# Power_Supply.net
KiCad netlist of a schematic drawn in Altium Designer
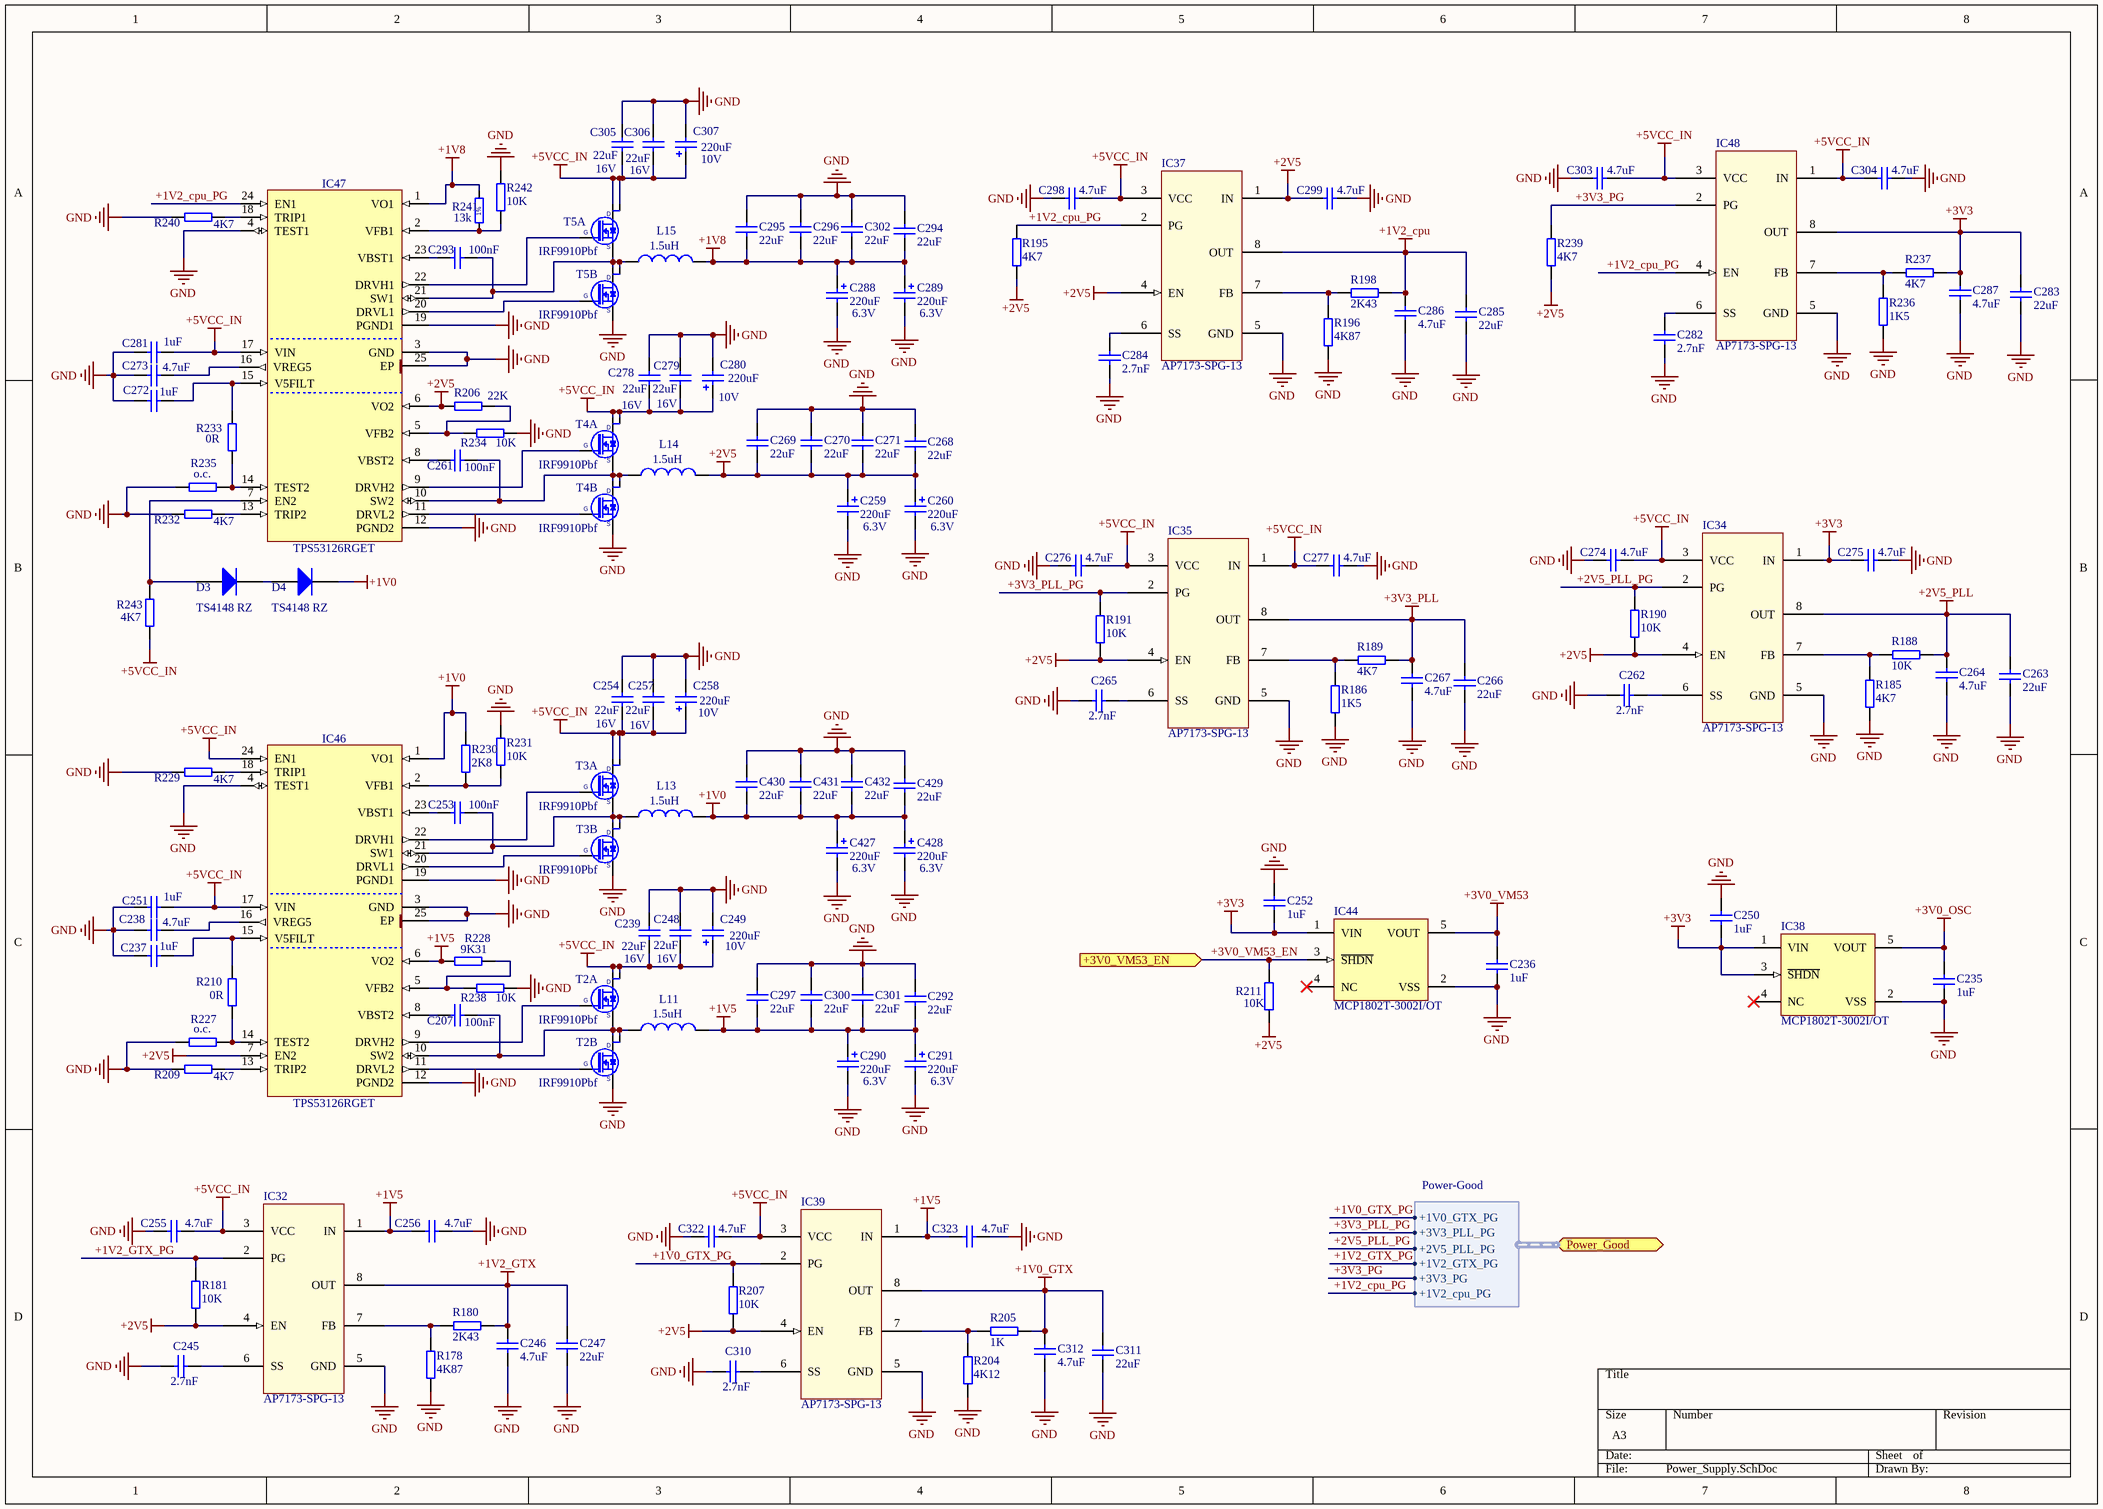
[diagram p0: Power_Supply.SchDoc]

(export (version "E")
  (design (tool "Eeschema 10.0.6"))
  (components
    (comp (ref "C207")
      (value "100nF")
      (footprint "CC1005-0402")
      (description "Capacitor")
      (fields
        (field (name "TOLERANCE") "±10%")
        (field (name "VOLTAGE") "16V")
        (field (name "PUBLISHER") "Altium Limited")
      )
      (libsource (lib "wr_switch") (part "Cap"))
    )
    (comp (ref "C235")
      (value "1uF")
      (footprint "CC1005-0402")
      (description "Capacitor")
      (fields
        (field (name "TOLERANCE") "±10%")
        (field (name "VOLTAGE") "16V")
        (field (name "PUBLISHER") "Altium Limited")
      )
      (libsource (lib "wr_switch") (part "Cap"))
    )
    (comp (ref "C236")
      (value "1uF")
      (footprint "CC1005-0402")
      (description "Capacitor")
      (fields
        (field (name "TOLERANCE") "±10%")
        (field (name "VOLTAGE") "16V")
        (field (name "PUBLISHER") "Altium Limited")
      )
      (libsource (lib "wr_switch") (part "Cap"))
    )
    (comp (ref "C237")
      (value "1uF")
      (footprint "CC1005-0402")
      (description "Capacitor")
      (fields
        (field (name "TOLERANCE") "±10%")
        (field (name "VOLTAGE") "16V")
        (field (name "PUBLISHER") "Altium Limited")
      )
      (libsource (lib "wr_switch") (part "Cap"))
    )
    (comp (ref "C238")
      (value "4.7uF")
      (footprint "CC1608-0603")
      (description "Capacitor")
      (fields
        (field (name "TOLERANCE") "±10%")
        (field (name "VOLTAGE") "10V")
        (field (name "PUBLISHER") "Altium Limited")
      )
      (libsource (lib "wr_switch") (part "Cap"))
    )
    (comp (ref "C239")
      (value "22uF")
      (footprint "CC2012-0805")
      (description "Capacitor")
      (fields
        (field (name "TOLERANCE") "±10%")
        (field (name "VOLTAGE") "16V")
        (field (name "Comment") "22uF 16V")
        (field (name "PUBLISHER") "Altium Limited")
      )
      (libsource (lib "wr_switch") (part "Cap"))
    )
    (comp (ref "C245")
      (value "2.7nF")
      (footprint "CC1005-0402")
      (description "Capacitor")
      (fields
        (field (name "TOLERANCE") "±10%")
        (field (name "VOLTAGE") "50V")
        (field (name "PUBLISHER") "Altium Limited")
      )
      (libsource (lib "wr_switch") (part "Cap"))
    )
    (comp (ref "C246")
      (value "4.7uF")
      (footprint "CC1608-0603")
      (description "Capacitor")
      (fields
        (field (name "TOLERANCE") "±10%")
        (field (name "VOLTAGE") "10V")
        (field (name "PUBLISHER") "Altium Limited")
      )
      (libsource (lib "wr_switch") (part "Cap"))
    )
    (comp (ref "C247")
      (value "22uF")
      (footprint "CC2012-0805")
      (description "Capacitor")
      (fields
        (field (name "TOLERANCE") "±20%")
        (field (name "VOLTAGE") "6.3V")
        (field (name "PUBLISHER") "Altium Limited")
      )
      (libsource (lib "wr_switch") (part "Cap"))
    )
    (comp (ref "C248")
      (value "22uF")
      (footprint "CC2012-0805")
      (description "Capacitor")
      (fields
        (field (name "TOLERANCE") "±10%")
        (field (name "VOLTAGE") "16V")
        (field (name "Comment") "22uF 16V")
        (field (name "PUBLISHER") "Altium Limited")
      )
      (libsource (lib "wr_switch") (part "Cap"))
    )
    (comp (ref "C249")
      (value "220uF")
      (footprint "D")
      (description "Polarized Capacitor Tantalum")
      (fields
        (field (name "TOLERANCE") "±20%")
        (field (name "VOLTAGE") "10V")
        (field (name "Comment") "220uF 10V")
        (field (name "PUBLISHER") "Altium Limited")
      )
      (libsource (lib "wr_switch") (part "Cap Pol1"))
    )
    (comp (ref "C250")
      (value "1uF")
      (footprint "CC1005-0402")
      (description "Capacitor")
      (fields
        (field (name "TOLERANCE") "±10%")
        (field (name "VOLTAGE") "16V")
        (field (name "PUBLISHER") "Altium Limited")
      )
      (libsource (lib "wr_switch") (part "Cap"))
    )
    (comp (ref "C251")
      (value "1uF")
      (footprint "CC1005-0402")
      (description "Capacitor")
      (fields
        (field (name "TOLERANCE") "±10%")
        (field (name "VOLTAGE") "16V")
        (field (name "PUBLISHER") "Altium Limited")
      )
      (libsource (lib "wr_switch") (part "Cap"))
    )
    (comp (ref "C252")
      (value "1uF")
      (footprint "CC1005-0402")
      (description "Capacitor")
      (fields
        (field (name "TOLERANCE") "±10%")
        (field (name "VOLTAGE") "16V")
        (field (name "PUBLISHER") "Altium Limited")
      )
      (libsource (lib "wr_switch") (part "Cap"))
    )
    (comp (ref "C253")
      (value "100nF")
      (footprint "CC1005-0402")
      (description "Capacitor")
      (fields
        (field (name "TOLERANCE") "±10%")
        (field (name "VOLTAGE") "16V")
        (field (name "PUBLISHER") "Altium Limited")
      )
      (libsource (lib "wr_switch") (part "Cap"))
    )
    (comp (ref "C254")
      (value "22uF")
      (footprint "CC2012-0805")
      (description "Capacitor")
      (fields
        (field (name "TOLERANCE") "±10%")
        (field (name "VOLTAGE") "16V")
        (field (name "Comment") "22uF 16V")
        (field (name "PUBLISHER") "Altium Limited")
      )
      (libsource (lib "wr_switch") (part "Cap"))
    )
    (comp (ref "C255")
      (value "4.7uF")
      (footprint "CC1608-0603")
      (description "Capacitor")
      (fields
        (field (name "TOLERANCE") "±10%")
        (field (name "VOLTAGE") "10V")
        (field (name "PUBLISHER") "Altium Limited")
      )
      (libsource (lib "wr_switch") (part "Cap"))
    )
    (comp (ref "C256")
      (value "4.7uF")
      (footprint "CC1608-0603")
      (description "Capacitor")
      (fields
        (field (name "TOLERANCE") "±10%")
        (field (name "VOLTAGE") "10V")
        (field (name "PUBLISHER") "Altium Limited")
      )
      (libsource (lib "wr_switch") (part "Cap"))
    )
    (comp (ref "C257")
      (value "22uF")
      (footprint "CC2012-0805")
      (description "Capacitor")
      (fields
        (field (name "TOLERANCE") "±10%")
        (field (name "VOLTAGE") "16V")
        (field (name "Comment") "22uF 16V")
        (field (name "PUBLISHER") "Altium Limited")
      )
      (libsource (lib "wr_switch") (part "Cap"))
    )
    (comp (ref "C258")
      (value "220uF")
      (footprint "D")
      (description "Polarized Capacitor Tantalum")
      (fields
        (field (name "TOLERANCE") "±20%")
        (field (name "VOLTAGE") "10V")
        (field (name "Comment") "220uF 10V")
        (field (name "PUBLISHER") "Altium Limited")
      )
      (libsource (lib "wr_switch") (part "Cap Pol1"))
    )
    (comp (ref "C259")
      (value "220uF")
      (footprint "D")
      (description "Polarized Capacitor Tantalum")
      (fields
        (field (name "TOLERANCE") "±20%")
        (field (name "VOLTAGE") "6.3V")
        (field (name "PUBLISHER") "Altium Limited")
      )
      (libsource (lib "wr_switch") (part "Cap Pol1"))
    )
    (comp (ref "C260")
      (value "220uF")
      (footprint "D")
      (description "Polarized Capacitor Tantalum")
      (fields
        (field (name "TOLERANCE") "±20%")
        (field (name "VOLTAGE") "6.3V")
        (field (name "PUBLISHER") "Altium Limited")
      )
      (libsource (lib "wr_switch") (part "Cap Pol1"))
    )
    (comp (ref "C261")
      (value "100nF")
      (footprint "CC1005-0402")
      (description "Capacitor")
      (fields
        (field (name "TOLERANCE") "±10%")
        (field (name "VOLTAGE") "16V")
        (field (name "PUBLISHER") "Altium Limited")
      )
      (libsource (lib "wr_switch") (part "Cap"))
    )
    (comp (ref "C262")
      (value "2.7nF")
      (footprint "CC1005-0402")
      (description "Capacitor")
      (fields
        (field (name "TOLERANCE") "±10%")
        (field (name "VOLTAGE") "50V")
        (field (name "PUBLISHER") "Altium Limited")
      )
      (libsource (lib "wr_switch") (part "Cap"))
    )
    (comp (ref "C263")
      (value "22uF")
      (footprint "CC2012-0805")
      (description "Capacitor")
      (fields
        (field (name "TOLERANCE") "±20%")
        (field (name "VOLTAGE") "6.3V")
        (field (name "PUBLISHER") "Altium Limited")
      )
      (libsource (lib "wr_switch") (part "Cap"))
    )
    (comp (ref "C264")
      (value "4.7uF")
      (footprint "CC1608-0603")
      (description "Capacitor")
      (fields
        (field (name "TOLERANCE") "±10%")
        (field (name "VOLTAGE") "10V")
        (field (name "PUBLISHER") "Altium Limited")
      )
      (libsource (lib "wr_switch") (part "Cap"))
    )
    (comp (ref "C265")
      (value "2.7nF")
      (footprint "CC1005-0402")
      (description "Capacitor")
      (fields
        (field (name "TOLERANCE") "±10%")
        (field (name "VOLTAGE") "50V")
        (field (name "PUBLISHER") "Altium Limited")
      )
      (libsource (lib "wr_switch") (part "Cap"))
    )
    (comp (ref "C266")
      (value "22uF")
      (footprint "CC2012-0805")
      (description "Capacitor")
      (fields
        (field (name "TOLERANCE") "±20%")
        (field (name "VOLTAGE") "6.3V")
        (field (name "PUBLISHER") "Altium Limited")
      )
      (libsource (lib "wr_switch") (part "Cap"))
    )
    (comp (ref "C267")
      (value "4.7uF")
      (footprint "CC1608-0603")
      (description "Capacitor")
      (fields
        (field (name "TOLERANCE") "±10%")
        (field (name "VOLTAGE") "10V")
        (field (name "PUBLISHER") "Altium Limited")
      )
      (libsource (lib "wr_switch") (part "Cap"))
    )
    (comp (ref "C268")
      (value "22uF")
      (footprint "CC2012-0805")
      (description "Capacitor")
      (fields
        (field (name "TOLERANCE") "±20%")
        (field (name "VOLTAGE") "6.3V")
        (field (name "PUBLISHER") "Altium Limited")
      )
      (libsource (lib "wr_switch") (part "Cap"))
    )
    (comp (ref "C269")
      (value "22uF")
      (footprint "CC2012-0805")
      (description "Capacitor")
      (fields
        (field (name "TOLERANCE") "±20%")
        (field (name "VOLTAGE") "6.3V")
        (field (name "PUBLISHER") "Altium Limited")
      )
      (libsource (lib "wr_switch") (part "Cap"))
    )
    (comp (ref "C270")
      (value "22uF")
      (footprint "CC2012-0805")
      (description "Capacitor")
      (fields
        (field (name "TOLERANCE") "±20%")
        (field (name "VOLTAGE") "6.3V")
        (field (name "PUBLISHER") "Altium Limited")
      )
      (libsource (lib "wr_switch") (part "Cap"))
    )
    (comp (ref "C271")
      (value "22uF")
      (footprint "CC2012-0805")
      (description "Capacitor")
      (fields
        (field (name "TOLERANCE") "±20%")
        (field (name "VOLTAGE") "6.3V")
        (field (name "PUBLISHER") "Altium Limited")
      )
      (libsource (lib "wr_switch") (part "Cap"))
    )
    (comp (ref "C272")
      (value "1uF")
      (footprint "CC1005-0402")
      (description "Capacitor")
      (fields
        (field (name "TOLERANCE") "±10%")
        (field (name "VOLTAGE") "16V")
        (field (name "PUBLISHER") "Altium Limited")
      )
      (libsource (lib "wr_switch") (part "Cap"))
    )
    (comp (ref "C273")
      (value "4.7uF")
      (footprint "CC1608-0603")
      (description "Capacitor")
      (fields
        (field (name "TOLERANCE") "±10%")
        (field (name "VOLTAGE") "10V")
        (field (name "PUBLISHER") "Altium Limited")
      )
      (libsource (lib "wr_switch") (part "Cap"))
    )
    (comp (ref "C274")
      (value "4.7uF")
      (footprint "CC1608-0603")
      (description "Capacitor")
      (fields
        (field (name "TOLERANCE") "±10%")
        (field (name "VOLTAGE") "10V")
        (field (name "PUBLISHER") "Altium Limited")
      )
      (libsource (lib "wr_switch") (part "Cap"))
    )
    (comp (ref "C275")
      (value "4.7uF")
      (footprint "CC1608-0603")
      (description "Capacitor")
      (fields
        (field (name "TOLERANCE") "±10%")
        (field (name "VOLTAGE") "10V")
        (field (name "PUBLISHER") "Altium Limited")
      )
      (libsource (lib "wr_switch") (part "Cap"))
    )
    (comp (ref "C276")
      (value "4.7uF")
      (footprint "CC1608-0603")
      (description "Capacitor")
      (fields
        (field (name "TOLERANCE") "±10%")
        (field (name "VOLTAGE") "10V")
        (field (name "PUBLISHER") "Altium Limited")
      )
      (libsource (lib "wr_switch") (part "Cap"))
    )
    (comp (ref "C277")
      (value "4.7uF")
      (footprint "CC1608-0603")
      (description "Capacitor")
      (fields
        (field (name "TOLERANCE") "±10%")
        (field (name "VOLTAGE") "10V")
        (field (name "PUBLISHER") "Altium Limited")
      )
      (libsource (lib "wr_switch") (part "Cap"))
    )
    (comp (ref "C278")
      (value "22uF")
      (footprint "CC2012-0805")
      (description "Capacitor")
      (fields
        (field (name "TOLERANCE") "±10%")
        (field (name "VOLTAGE") "16V")
        (field (name "Comment") "22uF 16V")
        (field (name "PUBLISHER") "Altium Limited")
      )
      (libsource (lib "wr_switch") (part "Cap"))
    )
    (comp (ref "C279")
      (value "22uF")
      (footprint "CC2012-0805")
      (description "Capacitor")
      (fields
        (field (name "TOLERANCE") "±10%")
        (field (name "VOLTAGE") "16V")
        (field (name "Comment") "22uF 16V")
        (field (name "PUBLISHER") "Altium Limited")
      )
      (libsource (lib "wr_switch") (part "Cap"))
    )
    (comp (ref "C280")
      (value "220uF")
      (footprint "D")
      (description "Polarized Capacitor Tantalum")
      (fields
        (field (name "TOLERANCE") "±20%")
        (field (name "VOLTAGE") "10V")
        (field (name "Comment") "220uF 10V")
        (field (name "PUBLISHER") "Altium Limited")
      )
      (libsource (lib "wr_switch") (part "Cap Pol1"))
    )
    (comp (ref "C281")
      (value "1uF")
      (footprint "CC1005-0402")
      (description "Capacitor")
      (fields
        (field (name "TOLERANCE") "±10%")
        (field (name "VOLTAGE") "16V")
        (field (name "PUBLISHER") "Altium Limited")
      )
      (libsource (lib "wr_switch") (part "Cap"))
    )
    (comp (ref "C282")
      (value "2.7nF")
      (footprint "CC1005-0402")
      (description "Capacitor")
      (fields
        (field (name "TOLERANCE") "±10%")
        (field (name "VOLTAGE") "50V")
        (field (name "PUBLISHER") "Altium Limited")
      )
      (libsource (lib "wr_switch") (part "Cap"))
    )
    (comp (ref "C283")
      (value "22uF")
      (footprint "CC2012-0805")
      (description "Capacitor")
      (fields
        (field (name "TOLERANCE") "±20%")
        (field (name "VOLTAGE") "6.3V")
        (field (name "PUBLISHER") "Altium Limited")
      )
      (libsource (lib "wr_switch") (part "Cap"))
    )
    (comp (ref "C284")
      (value "2.7nF")
      (footprint "CC1005-0402")
      (description "Capacitor")
      (fields
        (field (name "TOLERANCE") "±10%")
        (field (name "VOLTAGE") "50V")
        (field (name "PUBLISHER") "Altium Limited")
      )
      (libsource (lib "wr_switch") (part "Cap"))
    )
    (comp (ref "C285")
      (value "22uF")
      (footprint "CC2012-0805")
      (description "Capacitor")
      (fields
        (field (name "TOLERANCE") "±20%")
        (field (name "VOLTAGE") "6.3V")
        (field (name "PUBLISHER") "Altium Limited")
      )
      (libsource (lib "wr_switch") (part "Cap"))
    )
    (comp (ref "C286")
      (value "4.7uF")
      (footprint "CC1608-0603")
      (description "Capacitor")
      (fields
        (field (name "TOLERANCE") "±10%")
        (field (name "VOLTAGE") "10V")
        (field (name "PUBLISHER") "Altium Limited")
      )
      (libsource (lib "wr_switch") (part "Cap"))
    )
    (comp (ref "C287")
      (value "4.7uF")
      (footprint "CC1608-0603")
      (description "Capacitor")
      (fields
        (field (name "TOLERANCE") "±10%")
        (field (name "VOLTAGE") "10V")
        (field (name "PUBLISHER") "Altium Limited")
      )
      (libsource (lib "wr_switch") (part "Cap"))
    )
    (comp (ref "C288")
      (value "220uF")
      (footprint "D")
      (description "Polarized Capacitor Tantalum")
      (fields
        (field (name "TOLERANCE") "±20%")
        (field (name "VOLTAGE") "6.3V")
        (field (name "PUBLISHER") "Altium Limited")
      )
      (libsource (lib "wr_switch") (part "Cap Pol1"))
    )
    (comp (ref "C289")
      (value "220uF")
      (footprint "D")
      (description "Polarized Capacitor Tantalum")
      (fields
        (field (name "TOLERANCE") "±20%")
        (field (name "VOLTAGE") "6.3V")
        (field (name "PUBLISHER") "Altium Limited")
      )
      (libsource (lib "wr_switch") (part "Cap Pol1"))
    )
    (comp (ref "C290")
      (value "220uF")
      (footprint "D")
      (description "Polarized Capacitor Tantalum")
      (fields
        (field (name "TOLERANCE") "±20%")
        (field (name "VOLTAGE") "6.3V")
        (field (name "PUBLISHER") "Altium Limited")
      )
      (libsource (lib "wr_switch") (part "Cap Pol1"))
    )
    (comp (ref "C291")
      (value "220uF")
      (footprint "D")
      (description "Polarized Capacitor Tantalum")
      (fields
        (field (name "TOLERANCE") "±20%")
        (field (name "VOLTAGE") "6.3V")
        (field (name "PUBLISHER") "Altium Limited")
      )
      (libsource (lib "wr_switch") (part "Cap Pol1"))
    )
    (comp (ref "C292")
      (value "22uF")
      (footprint "CC2012-0805")
      (description "Capacitor")
      (fields
        (field (name "TOLERANCE") "±20%")
        (field (name "VOLTAGE") "6.3V")
        (field (name "PUBLISHER") "Altium Limited")
      )
      (libsource (lib "wr_switch") (part "Cap"))
    )
    (comp (ref "C293")
      (value "100nF")
      (footprint "CC1005-0402")
      (description "Capacitor")
      (fields
        (field (name "TOLERANCE") "±10%")
        (field (name "VOLTAGE") "16V")
        (field (name "PUBLISHER") "Altium Limited")
      )
      (libsource (lib "wr_switch") (part "Cap"))
    )
    (comp (ref "C294")
      (value "22uF")
      (footprint "CC2012-0805")
      (description "Capacitor")
      (fields
        (field (name "TOLERANCE") "±20%")
        (field (name "VOLTAGE") "6.3V")
        (field (name "PUBLISHER") "Altium Limited")
      )
      (libsource (lib "wr_switch") (part "Cap"))
    )
    (comp (ref "C295")
      (value "22uF")
      (footprint "CC2012-0805")
      (description "Capacitor")
      (fields
        (field (name "TOLERANCE") "±20%")
        (field (name "VOLTAGE") "6.3V")
        (field (name "PUBLISHER") "Altium Limited")
      )
      (libsource (lib "wr_switch") (part "Cap"))
    )
    (comp (ref "C296")
      (value "22uF")
      (footprint "CC2012-0805")
      (description "Capacitor")
      (fields
        (field (name "TOLERANCE") "±20%")
        (field (name "VOLTAGE") "6.3V")
        (field (name "PUBLISHER") "Altium Limited")
      )
      (libsource (lib "wr_switch") (part "Cap"))
    )
    (comp (ref "C297")
      (value "22uF")
      (footprint "CC2012-0805")
      (description "Capacitor")
      (fields
        (field (name "TOLERANCE") "±20%")
        (field (name "VOLTAGE") "6.3V")
        (field (name "PUBLISHER") "Altium Limited")
      )
      (libsource (lib "wr_switch") (part "Cap"))
    )
    (comp (ref "C298")
      (value "4.7uF")
      (footprint "CC1608-0603")
      (description "Capacitor")
      (fields
        (field (name "TOLERANCE") "±10%")
        (field (name "VOLTAGE") "10V")
        (field (name "PUBLISHER") "Altium Limited")
      )
      (libsource (lib "wr_switch") (part "Cap"))
    )
    (comp (ref "C299")
      (value "4.7uF")
      (footprint "CC1608-0603")
      (description "Capacitor")
      (fields
        (field (name "TOLERANCE") "±10%")
        (field (name "VOLTAGE") "10V")
        (field (name "PUBLISHER") "Altium Limited")
      )
      (libsource (lib "wr_switch") (part "Cap"))
    )
    (comp (ref "C300")
      (value "22uF")
      (footprint "CC2012-0805")
      (description "Capacitor")
      (fields
        (field (name "TOLERANCE") "±20%")
        (field (name "VOLTAGE") "6.3V")
        (field (name "PUBLISHER") "Altium Limited")
      )
      (libsource (lib "wr_switch") (part "Cap"))
    )
    (comp (ref "C301")
      (value "22uF")
      (footprint "CC2012-0805")
      (description "Capacitor")
      (fields
        (field (name "TOLERANCE") "±20%")
        (field (name "VOLTAGE") "6.3V")
        (field (name "PUBLISHER") "Altium Limited")
      )
      (libsource (lib "wr_switch") (part "Cap"))
    )
    (comp (ref "C302")
      (value "22uF")
      (footprint "CC2012-0805")
      (description "Capacitor")
      (fields
        (field (name "TOLERANCE") "±20%")
        (field (name "VOLTAGE") "6.3V")
        (field (name "PUBLISHER") "Altium Limited")
      )
      (libsource (lib "wr_switch") (part "Cap"))
    )
    (comp (ref "C303")
      (value "4.7uF")
      (footprint "CC1608-0603")
      (description "Capacitor")
      (fields
        (field (name "TOLERANCE") "±10%")
        (field (name "VOLTAGE") "10V")
        (field (name "PUBLISHER") "Altium Limited")
      )
      (libsource (lib "wr_switch") (part "Cap"))
    )
    (comp (ref "C304")
      (value "4.7uF")
      (footprint "CC1608-0603")
      (description "Capacitor")
      (fields
        (field (name "TOLERANCE") "±10%")
        (field (name "VOLTAGE") "10V")
        (field (name "PUBLISHER") "Altium Limited")
      )
      (libsource (lib "wr_switch") (part "Cap"))
    )
    (comp (ref "C305")
      (value "22uF")
      (footprint "CC2012-0805")
      (description "Capacitor")
      (fields
        (field (name "TOLERANCE") "±10%")
        (field (name "VOLTAGE") "16V")
        (field (name "Comment") "22uF 16V")
        (field (name "PUBLISHER") "Altium Limited")
      )
      (libsource (lib "wr_switch") (part "Cap"))
    )
    (comp (ref "C306")
      (value "22uF")
      (footprint "CC2012-0805")
      (description "Capacitor")
      (fields
        (field (name "TOLERANCE") "±10%")
        (field (name "VOLTAGE") "16V")
        (field (name "Comment") "22uF 16V")
        (field (name "PUBLISHER") "Altium Limited")
      )
      (libsource (lib "wr_switch") (part "Cap"))
    )
    (comp (ref "C307")
      (value "220uF")
      (footprint "D")
      (description "Polarized Capacitor Tantalum")
      (fields
        (field (name "TOLERANCE") "±20%")
        (field (name "VOLTAGE") "10V")
        (field (name "Comment") "220uF 10V")
        (field (name "PUBLISHER") "Altium Limited")
      )
      (libsource (lib "wr_switch") (part "Cap Pol1"))
    )
    (comp (ref "C310")
      (value "2.7nF")
      (footprint "CC1005-0402")
      (description "Capacitor")
      (fields
        (field (name "TOLERANCE") "±10%")
        (field (name "VOLTAGE") "50V")
        (field (name "PUBLISHER") "Altium Limited")
      )
      (libsource (lib "wr_switch") (part "Cap"))
    )
    (comp (ref "C311")
      (value "22uF")
      (footprint "CC2012-0805")
      (description "Capacitor")
      (fields
        (field (name "TOLERANCE") "±20%")
        (field (name "VOLTAGE") "6.3V")
        (field (name "PUBLISHER") "Altium Limited")
      )
      (libsource (lib "wr_switch") (part "Cap"))
    )
    (comp (ref "C312")
      (value "4.7uF")
      (footprint "CC1608-0603")
      (description "Capacitor")
      (fields
        (field (name "TOLERANCE") "±10%")
        (field (name "VOLTAGE") "10V")
        (field (name "PUBLISHER") "Altium Limited")
      )
      (libsource (lib "wr_switch") (part "Cap"))
    )
    (comp (ref "C322")
      (value "4.7uF")
      (footprint "CC1608-0603")
      (description "Capacitor")
      (fields
        (field (name "TOLERANCE") "±10%")
        (field (name "VOLTAGE") "10V")
        (field (name "PUBLISHER") "Altium Limited")
      )
      (libsource (lib "wr_switch") (part "Cap"))
    )
    (comp (ref "C323")
      (value "4.7uF")
      (footprint "CC1608-0603")
      (description "Capacitor")
      (fields
        (field (name "TOLERANCE") "±10%")
        (field (name "VOLTAGE") "10V")
        (field (name "PUBLISHER") "Altium Limited")
      )
      (libsource (lib "wr_switch") (part "Cap"))
    )
    (comp (ref "C427")
      (value "220uF")
      (footprint "D")
      (description "Polarized Capacitor Tantalum")
      (fields
        (field (name "TOLERANCE") "±20%")
        (field (name "VOLTAGE") "6.3V")
        (field (name "PUBLISHER") "Altium Limited")
      )
      (libsource (lib "wr_switch") (part "Cap Pol1"))
    )
    (comp (ref "C428")
      (value "220uF")
      (footprint "D")
      (description "Polarized Capacitor Tantalum")
      (fields
        (field (name "TOLERANCE") "±20%")
        (field (name "VOLTAGE") "6.3V")
        (field (name "PUBLISHER") "Altium Limited")
      )
      (libsource (lib "wr_switch") (part "Cap Pol1"))
    )
    (comp (ref "C429")
      (value "22uF")
      (footprint "CC2012-0805")
      (description "Capacitor")
      (fields
        (field (name "TOLERANCE") "±20%")
        (field (name "VOLTAGE") "6.3V")
        (field (name "PUBLISHER") "Altium Limited")
      )
      (libsource (lib "wr_switch") (part "Cap"))
    )
    (comp (ref "C430")
      (value "22uF")
      (footprint "CC2012-0805")
      (description "Capacitor")
      (fields
        (field (name "TOLERANCE") "±20%")
        (field (name "VOLTAGE") "6.3V")
        (field (name "PUBLISHER") "Altium Limited")
      )
      (libsource (lib "wr_switch") (part "Cap"))
    )
    (comp (ref "C431")
      (value "22uF")
      (footprint "CC2012-0805")
      (description "Capacitor")
      (fields
        (field (name "TOLERANCE") "±20%")
        (field (name "VOLTAGE") "6.3V")
        (field (name "PUBLISHER") "Altium Limited")
      )
      (libsource (lib "wr_switch") (part "Cap"))
    )
    (comp (ref "C432")
      (value "22uF")
      (footprint "CC2012-0805")
      (description "Capacitor")
      (fields
        (field (name "TOLERANCE") "±20%")
        (field (name "VOLTAGE") "6.3V")
        (field (name "PUBLISHER") "Altium Limited")
      )
      (libsource (lib "wr_switch") (part "Cap"))
    )
    (comp (ref "D3")
      (value "TS4148 RZ")
      (footprint "CC1608-0603")
      (description "Default Diode")
      (fields (field (name "PUBLISHER") "Altium Limited"))
      (libsource (lib "Miscellaneous Devices") (part "Diode"))
    )
    (comp (ref "D4")
      (value "TS4148 RZ")
      (footprint "CC1608-0603")
      (description "Default Diode")
      (fields (field (name "PUBLISHER") "Altium Limited"))
      (libsource (lib "Miscellaneous Devices") (part "Diode"))
    )
    (comp (ref "IC32")
      (value "AP7173-SPG-13")
      (footprint "SOIC127P600-8AL")
      (description "1.5A Low Dropout Linera Regulator")
      (libsource (lib "wr_switch") (part "AP7173"))
    )
    (comp (ref "IC34")
      (value "AP7173-SPG-13")
      (footprint "SOIC127P600-8AL")
      (description "1.5A Low Dropout Linera Regulator")
      (libsource (lib "wr_switch") (part "AP7173"))
    )
    (comp (ref "IC35")
      (value "AP7173-SPG-13")
      (footprint "SOIC127P600-8AL")
      (description "1.5A Low Dropout Linera Regulator")
      (libsource (lib "wr_switch") (part "AP7173"))
    )
    (comp (ref "IC37")
      (value "AP7173-SPG-13")
      (footprint "SOIC127P600-8AL")
      (description "1.5A Low Dropout Linera Regulator")
      (libsource (lib "wr_switch") (part "AP7173"))
    )
    (comp (ref "IC38")
      (value "MCP1802T-3002I/OT")
      (footprint "SOT-23-OT5_N")
      (description "300 mA, High PSRR, Low Quiescent Current LDO, 5-Pin SOT-23, Industrial Temperature, Tape and Reel")
      (fields (field (name "PUBLISHER") "Altium Limited"))
      (libsource (lib "Microchip Power Mgt Line Regulator") (part "MCP1802T-3002I/OT"))
    )
    (comp (ref "IC39")
      (value "AP7173-SPG-13")
      (footprint "SOIC127P600-8AL")
      (description "1.5A Low Dropout Linera Regulator")
      (libsource (lib "wr_switch") (part "AP7173"))
    )
    (comp (ref "IC44")
      (value "MCP1802T-3002I/OT")
      (footprint "SOT-23-OT5_N")
      (description "300 mA, High PSRR, Low Quiescent Current LDO, 5-Pin SOT-23, Industrial Temperature, Tape and Reel")
      (fields (field (name "PUBLISHER") "Altium Limited"))
      (libsource (lib "Microchip Power Mgt Line Regulator") (part "MCP1802T-3002I/OT"))
    )
    (comp (ref "IC46")
      (value "TPS53126RGET")
      (footprint "QFN50P400X400X100-25N-S255")
      (description "Dual Synchronous Step-Down Controller For Low Voltage Power Rails")
      (fields (field (name "MANUFACTURER") "TEXAS INSTRUMENTS") (field (name "AUTHOR") "CERN DEM JLC"))
      (libsource (lib "wr_switch") (part "TPS53126RGET"))
    )
    (comp (ref "IC47")
      (value "TPS53126RGET")
      (footprint "QFN50P400X400X100-25N-S255")
      (description "Dual Synchronous Step-Down Controller For Low Voltage Power Rails")
      (fields (field (name "MANUFACTURER") "TEXAS INSTRUMENTS") (field (name "AUTHOR") "CERN DEM JLC"))
      (libsource (lib "wr_switch") (part "TPS53126RGET"))
    )
    (comp (ref "IC48")
      (value "AP7173-SPG-13")
      (footprint "SOIC127P600-8AL")
      (description "1.5A Low Dropout Linera Regulator")
      (libsource (lib "wr_switch") (part "AP7173"))
    )
    (comp (ref "L11")
      (value "1.5uH")
      (footprint "IHLP2525")
      (description "Low Profile, High Current Inductor")
      (fields
        (field (name "MANUFACTURER") "Vishay/Dale")
        (field (name "Comment") "IHLP2525CZER1R0M01")
        (field (name "PUBLISHER") "Altium Limited")
      )
      (libsource (lib "Miscellaneous Devices") (part "Inductor"))
    )
    (comp (ref "L13")
      (value "1.5uH")
      (footprint "IHLP2525")
      (description "Low Profile, High Current Inductor")
      (fields
        (field (name "MANUFACTURER") "Vishay/Dale")
        (field (name "Comment") "IHLP2525CZER1R0M01")
        (field (name "PUBLISHER") "Altium Limited")
      )
      (libsource (lib "Miscellaneous Devices") (part "Inductor"))
    )
    (comp (ref "L14")
      (value "1.5uH")
      (footprint "IHLP2525")
      (description "Low Profile, High Current Inductor")
      (fields
        (field (name "MANUFACTURER") "Vishay/Dale")
        (field (name "Comment") "IHLP2525CZER1R0M01")
        (field (name "PUBLISHER") "Altium Limited")
      )
      (libsource (lib "Miscellaneous Devices") (part "Inductor"))
    )
    (comp (ref "L15")
      (value "1.5uH")
      (footprint "IHLP2525")
      (description "Low Profile, High Current Inductor")
      (fields
        (field (name "MANUFACTURER") "Vishay/Dale")
        (field (name "Comment") "IHLP2525CZER1R0M01")
        (field (name "PUBLISHER") "Altium Limited")
      )
      (libsource (lib "Miscellaneous Devices") (part "Inductor"))
    )
    (comp (ref "R178")
      (value "4K87")
      (footprint "0402")
      (description "SMD Resistor")
      (fields (field (name "TOLERANCE") "±1%"))
      (libsource (lib "wr_switch") (part "RES_SMD"))
    )
    (comp (ref "R180")
      (value "2K43")
      (footprint "0402")
      (description "SMD Resistor")
      (fields (field (name "TOLERANCE") "±1%"))
      (libsource (lib "wr_switch") (part "RES_SMD"))
    )
    (comp (ref "R181")
      (value "10K")
      (footprint "0402")
      (description "SMD Resistor")
      (fields (field (name "TOLERANCE") "±1%") (field (name "Comment") "10k"))
      (libsource (lib "wr_switch") (part "RES_SMD"))
    )
    (comp (ref "R185")
      (value "4K7")
      (footprint "0402")
      (description "SMD Resistor")
      (fields (field (name "TOLERANCE") "±1%"))
      (libsource (lib "wr_switch") (part "RES_SMD"))
    )
    (comp (ref "R186")
      (value "1K5")
      (footprint "0402")
      (description "SMD Resistor")
      (fields (field (name "TOLERANCE") "±1%"))
      (libsource (lib "wr_switch") (part "RES_SMD"))
    )
    (comp (ref "R188")
      (value "10K")
      (footprint "0402")
      (description "SMD Resistor")
      (fields (field (name "TOLERANCE") "±1%"))
      (libsource (lib "wr_switch") (part "RES_SMD"))
    )
    (comp (ref "R189")
      (value "4K7")
      (footprint "0402")
      (description "SMD Resistor")
      (fields (field (name "TOLERANCE") "±1%"))
      (libsource (lib "wr_switch") (part "RES_SMD"))
    )
    (comp (ref "R190")
      (value "10K")
      (footprint "0402")
      (description "SMD Resistor")
      (fields (field (name "TOLERANCE") "±1%") (field (name "Comment") "10k"))
      (libsource (lib "wr_switch") (part "RES_SMD"))
    )
    (comp (ref "R191")
      (value "10K")
      (footprint "0402")
      (description "SMD Resistor")
      (fields (field (name "TOLERANCE") "±1%") (field (name "Comment") "10k"))
      (libsource (lib "wr_switch") (part "RES_SMD"))
    )
    (comp (ref "R195")
      (value "4K7")
      (footprint "0402")
      (description "SMD Resistor")
      (fields (field (name "TOLERANCE") "±1%"))
      (libsource (lib "wr_switch") (part "RES_SMD"))
    )
    (comp (ref "R196")
      (value "4K87")
      (footprint "0402")
      (description "SMD Resistor")
      (fields (field (name "TOLERANCE") "±1%"))
      (libsource (lib "wr_switch") (part "RES_SMD"))
    )
    (comp (ref "R198")
      (value "2K43")
      (footprint "0402")
      (description "SMD Resistor")
      (fields (field (name "TOLERANCE") "±1%"))
      (libsource (lib "wr_switch") (part "RES_SMD"))
    )
    (comp (ref "R204")
      (value "4K12")
      (footprint "0402")
      (description "SMD Resistor")
      (fields (field (name "TOLERANCE") "±1%"))
      (libsource (lib "wr_switch") (part "RES_SMD"))
    )
    (comp (ref "R205")
      (value "1K")
      (footprint "0402")
      (description "SMD Resistor")
      (fields (field (name "TOLERANCE") "±1%"))
      (libsource (lib "wr_switch") (part "RES_SMD"))
    )
    (comp (ref "R206")
      (value "22K")
      (footprint "0402")
      (description "SMD Resistor")
      (fields (field (name "TOLERANCE") "±1%"))
      (libsource (lib "wr_switch") (part "RES_SMD"))
    )
    (comp (ref "R207")
      (value "10K")
      (footprint "0402")
      (description "SMD Resistor")
      (fields (field (name "TOLERANCE") "±1%"))
      (libsource (lib "wr_switch") (part "RES_SMD"))
    )
    (comp (ref "R209")
      (value "4K7")
      (footprint "0402")
      (description "SMD Resistor")
      (fields (field (name "TOLERANCE") "±1%"))
      (libsource (lib "wr_switch") (part "RES_SMD"))
    )
    (comp (ref "R210")
      (value "0R")
      (footprint "0402")
      (description "SMD Resistor")
      (fields (field (name "TOLERANCE") "Jumper"))
      (libsource (lib "wr_switch") (part "RES_SMD"))
    )
    (comp (ref "R211")
      (value "10K")
      (footprint "0402")
      (description "SMD Resistor")
      (fields (field (name "TOLERANCE") "±1%") (field (name "Comment") "10k"))
      (libsource (lib "wr_switch") (part "RES_SMD"))
    )
    (comp (ref "R227")
      (value "o.c.")
      (footprint "0402")
      (description "SMD Resistor")
      (libsource (lib "wr_switch") (part "RES_SMD"))
    )
    (comp (ref "R228")
      (value "9K31")
      (footprint "0402")
      (description "SMD Resistor")
      (fields (field (name "TOLERANCE") "±1%"))
      (libsource (lib "wr_switch") (part "RES_SMD"))
    )
    (comp (ref "R229")
      (value "4K7")
      (footprint "0402")
      (description "SMD Resistor")
      (fields (field (name "TOLERANCE") "±1%"))
      (libsource (lib "wr_switch") (part "RES_SMD"))
    )
    (comp (ref "R230")
      (value "2K8")
      (footprint "0402")
      (description "SMD Resistor")
      (fields (field (name "TOLERANCE") "±1%"))
      (libsource (lib "wr_switch") (part "RES_SMD"))
    )
    (comp (ref "R231")
      (value "10K")
      (footprint "0402")
      (description "SMD Resistor")
      (fields (field (name "TOLERANCE") "±1%"))
      (libsource (lib "wr_switch") (part "RES_SMD"))
    )
    (comp (ref "R232")
      (value "4K7")
      (footprint "0402")
      (description "SMD Resistor")
      (fields (field (name "TOLERANCE") "±1%"))
      (libsource (lib "wr_switch") (part "RES_SMD"))
    )
    (comp (ref "R233")
      (value "0R")
      (footprint "0402")
      (description "SMD Resistor")
      (fields (field (name "TOLERANCE") "Jumper"))
      (libsource (lib "wr_switch") (part "RES_SMD"))
    )
    (comp (ref "R234")
      (value "10K")
      (footprint "0402")
      (description "SMD Resistor")
      (fields (field (name "TOLERANCE") "±1%"))
      (libsource (lib "wr_switch") (part "RES_SMD"))
    )
    (comp (ref "R235")
      (value "o.c.")
      (footprint "0402")
      (description "SMD Resistor")
      (libsource (lib "wr_switch") (part "RES_SMD"))
    )
    (comp (ref "R236")
      (value "1K5")
      (footprint "0402")
      (description "SMD Resistor")
      (fields (field (name "TOLERANCE") "±1%"))
      (libsource (lib "wr_switch") (part "RES_SMD"))
    )
    (comp (ref "R237")
      (value "4K7")
      (footprint "0402")
      (description "SMD Resistor")
      (fields (field (name "TOLERANCE") "±1%"))
      (libsource (lib "wr_switch") (part "RES_SMD"))
    )
    (comp (ref "R238")
      (value "10K")
      (footprint "0402")
      (description "SMD Resistor")
      (fields (field (name "TOLERANCE") "±1%"))
      (libsource (lib "wr_switch") (part "RES_SMD"))
    )
    (comp (ref "R239")
      (value "4K7")
      (footprint "0402")
      (description "SMD Resistor")
      (fields (field (name "TOLERANCE") "±1%"))
      (libsource (lib "wr_switch") (part "RES_SMD"))
    )
    (comp (ref "R240")
      (value "4K7")
      (footprint "0402")
      (description "SMD Resistor")
      (fields (field (name "TOLERANCE") "±1%"))
      (libsource (lib "wr_switch") (part "RES_SMD"))
    )
    (comp (ref "R241")
      (value "13k")
      (footprint "RESC1005X40N")
      (description "Resistor - 1%")
      (fields
        (field (name "PART NUMBER") "R0402_13K_1%_0.0625W_100PPM")
        (field (name "POWER") "0.0625W")
        (field (name "AUTHOR") "CERN DEM JLC")
      )
      (libsource (lib "Resistors") (part "Resistor - 1%"))
    )
    (comp (ref "R242")
      (value "10K")
      (footprint "0402")
      (description "SMD Resistor")
      (fields (field (name "TOLERANCE") "±1%"))
      (libsource (lib "wr_switch") (part "RES_SMD"))
    )
    (comp (ref "R243")
      (value "4K7")
      (footprint "0402")
      (description "SMD Resistor")
      (fields (field (name "TOLERANCE") "±1%"))
      (libsource (lib "wr_switch") (part "RES_SMD"))
    )
    (comp (ref "T2")
      (value "IRF9910Pbf")
      (footprint "SOIC127P600X175-8N")
      (description "Dual SO-8 MOSFET For POL Cconverter")
      (fields (field (name "MANUFACTURER") "INTERNATIONAL RECTIFIER") (field (name "AUTHOR") "CERN DEM JLC"))
      (libsource (lib "ICs And Semiconductors") (part "IRF9910"))
    )
    (comp (ref "T3")
      (value "IRF9910Pbf")
      (footprint "SOIC127P600X175-8N")
      (description "Dual SO-8 MOSFET For POL Cconverter")
      (fields (field (name "MANUFACTURER") "INTERNATIONAL RECTIFIER") (field (name "AUTHOR") "CERN DEM JLC"))
      (libsource (lib "ICs And Semiconductors") (part "IRF9910"))
    )
    (comp (ref "T4")
      (value "IRF9910Pbf")
      (footprint "SOIC127P600X175-8N")
      (description "Dual SO-8 MOSFET For POL Cconverter")
      (fields (field (name "MANUFACTURER") "INTERNATIONAL RECTIFIER") (field (name "AUTHOR") "CERN DEM JLC"))
      (libsource (lib "ICs And Semiconductors") (part "IRF9910"))
    )
    (comp (ref "T5")
      (value "IRF9910Pbf")
      (footprint "SOIC127P600X175-8N")
      (description "Dual SO-8 MOSFET For POL Cconverter")
      (fields (field (name "MANUFACTURER") "INTERNATIONAL RECTIFIER") (field (name "AUTHOR") "CERN DEM JLC"))
      (libsource (lib "ICs And Semiconductors") (part "IRF9910"))
    )
  )
  (nets
    (net (code "2") (name "+1V0") (class "Default")
      (node (ref "C427") (pin "1") (pinfunction "1_1") (pintype "passive"))
      (node (ref "C428") (pin "1") (pinfunction "1_1") (pintype "passive"))
      (node (ref "C429") (pin "1") (pinfunction "1_1") (pintype "passive"))
      (node (ref "C430") (pin "2") (pinfunction "2_2") (pintype "passive"))
      (node (ref "C431") (pin "1") (pinfunction "1_1") (pintype "passive"))
      (node (ref "C432") (pin "1") (pinfunction "1_1") (pintype "passive"))
      (node (ref "D4") (pin "2") (pinfunction "K_2") (pintype "passive"))
      (node (ref "IC46") (pin "1") (pinfunction "VO1_1") (pintype "input"))
      (node (ref "L13") (pin "2") (pinfunction "2_2") (pintype "passive"))
      (node (ref "R230") (pin "2") (pinfunction "2_2") (pintype "passive"))
    )
    (net (code "3") (name "+1V0_GTX") (class "Default")
      (node (ref "C311") (pin "2") (pinfunction "2_2") (pintype "passive"))
      (node (ref "C312") (pin "2") (pinfunction "2_2") (pintype "passive"))
      (node (ref "IC39") (pin "8") (pinfunction "OUT_8") (pintype "power_in"))
      (node (ref "R205") (pin "2") (pinfunction "2_2") (pintype "passive"))
    )
    (net (code "4") (name "+1V2_GTX") (class "Default")
      (node (ref "C246") (pin "2") (pinfunction "2_2") (pintype "passive"))
      (node (ref "C247") (pin "2") (pinfunction "2_2") (pintype "passive"))
      (node (ref "IC32") (pin "8") (pinfunction "OUT_8") (pintype "power_in"))
      (node (ref "R180") (pin "2") (pinfunction "2_2") (pintype "passive"))
    )
    (net (code "5") (name "+1V2_cpu") (class "Default")
      (node (ref "C285") (pin "2") (pinfunction "2_2") (pintype "passive"))
      (node (ref "C286") (pin "2") (pinfunction "2_2") (pintype "passive"))
      (node (ref "IC37") (pin "8") (pinfunction "OUT_8") (pintype "power_in"))
      (node (ref "R198") (pin "2") (pinfunction "2_2") (pintype "passive"))
    )
    (net (code "6") (name "+1V5") (class "Default")
      (node (ref "C256") (pin "1") (pinfunction "1_1") (pintype "passive"))
      (node (ref "C290") (pin "1") (pinfunction "1_1") (pintype "passive"))
      (node (ref "C291") (pin "1") (pinfunction "1_1") (pintype "passive"))
      (node (ref "C292") (pin "1") (pinfunction "1_1") (pintype "passive"))
      (node (ref "C297") (pin "2") (pinfunction "2_2") (pintype "passive"))
      (node (ref "C300") (pin "1") (pinfunction "1_1") (pintype "passive"))
      (node (ref "C301") (pin "1") (pinfunction "1_1") (pintype "passive"))
      (node (ref "C323") (pin "1") (pinfunction "1_1") (pintype "passive"))
      (node (ref "IC32") (pin "1") (pinfunction "IN_1") (pintype "power_in"))
      (node (ref "IC39") (pin "1") (pinfunction "IN_1") (pintype "power_in"))
      (node (ref "IC46") (pin "6") (pinfunction "VO2_6") (pintype "input"))
      (node (ref "L11") (pin "2") (pinfunction "2_2") (pintype "passive"))
      (node (ref "R228") (pin "1") (pinfunction "1_1") (pintype "passive"))
    )
    (net (code "7") (name "+1V8") (class "Default")
      (node (ref "C288") (pin "1") (pinfunction "1_1") (pintype "passive"))
      (node (ref "C289") (pin "1") (pinfunction "1_1") (pintype "passive"))
      (node (ref "C294") (pin "1") (pinfunction "1_1") (pintype "passive"))
      (node (ref "C295") (pin "2") (pinfunction "2_2") (pintype "passive"))
      (node (ref "C296") (pin "1") (pinfunction "1_1") (pintype "passive"))
      (node (ref "C302") (pin "1") (pinfunction "1_1") (pintype "passive"))
      (node (ref "IC47") (pin "1") (pinfunction "VO1_1") (pintype "input"))
      (node (ref "L15") (pin "2") (pinfunction "2_2") (pintype "passive"))
      (node (ref "R241") (pin "2") (pinfunction "2_2") (pintype "passive"))
    )
    (net (code "8") (name "+2V5") (class "Default")
      (node (ref "C259") (pin "1") (pinfunction "1_1") (pintype "passive"))
      (node (ref "C260") (pin "1") (pinfunction "1_1") (pintype "passive"))
      (node (ref "C268") (pin "1") (pinfunction "1_1") (pintype "passive"))
      (node (ref "C269") (pin "2") (pinfunction "2_2") (pintype "passive"))
      (node (ref "C270") (pin "1") (pinfunction "1_1") (pintype "passive"))
      (node (ref "C271") (pin "1") (pinfunction "1_1") (pintype "passive"))
      (node (ref "C299") (pin "1") (pinfunction "1_1") (pintype "passive"))
      (node (ref "IC32") (pin "4") (pinfunction "EN_4") (pintype "input"))
      (node (ref "IC34") (pin "4") (pinfunction "EN_4") (pintype "input"))
      (node (ref "IC35") (pin "4") (pinfunction "EN_4") (pintype "input"))
      (node (ref "IC37") (pin "1") (pinfunction "IN_1") (pintype "power_in"))
      (node (ref "IC37") (pin "4") (pinfunction "EN_4") (pintype "input"))
      (node (ref "IC39") (pin "4") (pinfunction "EN_4") (pintype "input"))
      (node (ref "IC46") (pin "7") (pinfunction "EN2_7") (pintype "input"))
      (node (ref "IC47") (pin "6") (pinfunction "VO2_6") (pintype "input"))
      (node (ref "L14") (pin "2") (pinfunction "2_2") (pintype "passive"))
      (node (ref "R181") (pin "1") (pinfunction "1_1") (pintype "passive"))
      (node (ref "R190") (pin "1") (pinfunction "1_1") (pintype "passive"))
      (node (ref "R191") (pin "1") (pinfunction "1_1") (pintype "passive"))
      (node (ref "R195") (pin "2") (pinfunction "2_2") (pintype "passive"))
      (node (ref "R206") (pin "2") (pinfunction "2_2") (pintype "passive"))
      (node (ref "R207") (pin "1") (pinfunction "1_1") (pintype "passive"))
      (node (ref "R211") (pin "2") (pinfunction "2_2") (pintype "passive"))
      (node (ref "R239") (pin "1") (pinfunction "1_1") (pintype "passive"))
    )
    (net (code "9") (name "+2V5_PLL") (class "Default")
      (node (ref "C263") (pin "2") (pinfunction "2_2") (pintype "passive"))
      (node (ref "C264") (pin "2") (pinfunction "2_2") (pintype "passive"))
      (node (ref "IC34") (pin "8") (pinfunction "OUT_8") (pintype "power_in"))
      (node (ref "R188") (pin "1") (pinfunction "1_1") (pintype "passive"))
    )
    (net (code "10") (name "+3V0_OSC") (class "Default")
      (node (ref "C235") (pin "2") (pinfunction "2_2") (pintype "passive"))
      (node (ref "IC38") (pin "5") (pinfunction "VOUT_5") (pintype "power_in"))
    )
    (net (code "11") (name "+3V0_VM53") (class "Default")
      (node (ref "C236") (pin "2") (pinfunction "2_2") (pintype "passive"))
      (node (ref "IC44") (pin "5") (pinfunction "VOUT_5") (pintype "power_in"))
    )
    (net (code "12") (name "+3V3") (class "Default")
      (node (ref "C250") (pin "2") (pinfunction "2_2") (pintype "passive"))
      (node (ref "C252") (pin "2") (pinfunction "2_2") (pintype "passive"))
      (node (ref "C275") (pin "1") (pinfunction "1_1") (pintype "passive"))
      (node (ref "C283") (pin "2") (pinfunction "2_2") (pintype "passive"))
      (node (ref "C287") (pin "2") (pinfunction "2_2") (pintype "passive"))
      (node (ref "IC34") (pin "1") (pinfunction "IN_1") (pintype "power_in"))
      (node (ref "IC38") (pin "1") (pinfunction "VIN_1") (pintype "power_in"))
      (node (ref "IC38") (pin "3") (pinfunction "~{SHDN}_3") (pintype "input"))
      (node (ref "IC44") (pin "1") (pinfunction "VIN_1") (pintype "power_in"))
      (node (ref "IC48") (pin "8") (pinfunction "OUT_8") (pintype "power_in"))
      (node (ref "R237") (pin "2") (pinfunction "2_2") (pintype "passive"))
    )
    (net (code "13") (name "+3V3_PLL") (class "Default")
      (node (ref "C266") (pin "2") (pinfunction "2_2") (pintype "passive"))
      (node (ref "C267") (pin "2") (pinfunction "2_2") (pintype "passive"))
      (node (ref "IC35") (pin "8") (pinfunction "OUT_8") (pintype "power_in"))
      (node (ref "R189") (pin "1") (pinfunction "1_1") (pintype "passive"))
    )
    (net (code "14") (name "+5VCC_IN") (class "Default")
      (node (ref "C239") (pin "1") (pinfunction "1_1") (pintype "passive"))
      (node (ref "C248") (pin "1") (pinfunction "1_1") (pintype "passive"))
      (node (ref "C249") (pin "1") (pinfunction "1_1") (pintype "passive"))
      (node (ref "C251") (pin "2") (pinfunction "2_2") (pintype "passive"))
      (node (ref "C254") (pin "1") (pinfunction "1_1") (pintype "passive"))
      (node (ref "C255") (pin "2") (pinfunction "2_2") (pintype "passive"))
      (node (ref "C257") (pin "1") (pinfunction "1_1") (pintype "passive"))
      (node (ref "C258") (pin "1") (pinfunction "1_1") (pintype "passive"))
      (node (ref "C274") (pin "2") (pinfunction "2_2") (pintype "passive"))
      (node (ref "C276") (pin "2") (pinfunction "2_2") (pintype "passive"))
      (node (ref "C277") (pin "1") (pinfunction "1_1") (pintype "passive"))
      (node (ref "C278") (pin "1") (pinfunction "1_1") (pintype "passive"))
      (node (ref "C279") (pin "1") (pinfunction "1_1") (pintype "passive"))
      (node (ref "C280") (pin "1") (pinfunction "1_1") (pintype "passive"))
      (node (ref "C281") (pin "2") (pinfunction "2_2") (pintype "passive"))
      (node (ref "C298") (pin "2") (pinfunction "2_2") (pintype "passive"))
      (node (ref "C303") (pin "2") (pinfunction "2_2") (pintype "passive"))
      (node (ref "C304") (pin "1") (pinfunction "1_1") (pintype "passive"))
      (node (ref "C305") (pin "1") (pinfunction "1_1") (pintype "passive"))
      (node (ref "C306") (pin "1") (pinfunction "1_1") (pintype "passive"))
      (node (ref "C307") (pin "1") (pinfunction "1_1") (pintype "passive"))
      (node (ref "C322") (pin "2") (pinfunction "2_2") (pintype "passive"))
      (node (ref "IC32") (pin "3") (pinfunction "VCC_3") (pintype "power_in"))
      (node (ref "IC34") (pin "3") (pinfunction "VCC_3") (pintype "power_in"))
      (node (ref "IC35") (pin "1") (pinfunction "IN_1") (pintype "power_in"))
      (node (ref "IC35") (pin "3") (pinfunction "VCC_3") (pintype "power_in"))
      (node (ref "IC37") (pin "3") (pinfunction "VCC_3") (pintype "power_in"))
      (node (ref "IC39") (pin "3") (pinfunction "VCC_3") (pintype "power_in"))
      (node (ref "IC46") (pin "17") (pinfunction "VIN_17") (pintype "input"))
      (node (ref "IC46") (pin "24") (pinfunction "EN1_24") (pintype "input"))
      (node (ref "IC47") (pin "17") (pinfunction "VIN_17") (pintype "input"))
      (node (ref "IC48") (pin "1") (pinfunction "IN_1") (pintype "power_in"))
      (node (ref "IC48") (pin "3") (pinfunction "VCC_3") (pintype "power_in"))
      (node (ref "R243") (pin "2") (pinfunction "2_2") (pintype "passive"))
      (node (ref "T2") (pin "5") (pinfunction "D_5") (pintype "passive"))
      (node (ref "T2") (pin "6") (pinfunction "D_6") (pintype "passive"))
      (node (ref "T3") (pin "5") (pinfunction "D_5") (pintype "passive"))
      (node (ref "T3") (pin "6") (pinfunction "D_6") (pintype "passive"))
      (node (ref "T4") (pin "5") (pinfunction "D_5") (pintype "passive"))
      (node (ref "T4") (pin "6") (pinfunction "D_6") (pintype "passive"))
      (node (ref "T5") (pin "5") (pinfunction "D_5") (pintype "passive"))
      (node (ref "T5") (pin "6") (pinfunction "D_6") (pintype "passive"))
    )
    (net (code "15") (name "/+1V0_GTX_PG") (class "Default")
      (node (ref "IC39") (pin "2") (pinfunction "PG_2") (pintype "open_collector"))
      (node (ref "R207") (pin "2") (pinfunction "2_2") (pintype "passive"))
    )
    (net (code "16") (name "/+1V2_GTX_PG") (class "Default")
      (node (ref "IC32") (pin "2") (pinfunction "PG_2") (pintype "open_collector"))
      (node (ref "R181") (pin "2") (pinfunction "2_2") (pintype "passive"))
    )
    (net (code "17") (name "/+1V2_cpu_PG") (class "Default")
      (node (ref "IC37") (pin "2") (pinfunction "PG_2") (pintype "open_collector"))
      (node (ref "IC47") (pin "24") (pinfunction "EN1_24") (pintype "input"))
      (node (ref "IC48") (pin "4") (pinfunction "EN_4") (pintype "input"))
      (node (ref "R195") (pin "1") (pinfunction "1_1") (pintype "passive"))
    )
    (net (code "18") (name "/+2V5_PLL_PG") (class "Default")
      (node (ref "IC34") (pin "2") (pinfunction "PG_2") (pintype "open_collector"))
      (node (ref "R190") (pin "2") (pinfunction "2_2") (pintype "passive"))
    )
    (net (code "19") (name "/+3V0_VM53_EN") (class "Default")
      (node (ref "IC44") (pin "3") (pinfunction "~{SHDN}_3") (pintype "input"))
      (node (ref "R211") (pin "1") (pinfunction "1_1") (pintype "passive"))
    )
    (net (code "20") (name "/+3V3_PG") (class "Default")
      (node (ref "IC48") (pin "2") (pinfunction "PG_2") (pintype "open_collector"))
      (node (ref "R239") (pin "2") (pinfunction "2_2") (pintype "passive"))
    )
    (net (code "21") (name "/+3V3_PLL_PG") (class "Default")
      (node (ref "IC35") (pin "2") (pinfunction "PG_2") (pintype "open_collector"))
      (node (ref "R191") (pin "2") (pinfunction "2_2") (pintype "passive"))
    )
    (net (code "23") (name "GND") (class "Default")
      (node (ref "C235") (pin "1") (pinfunction "1_1") (pintype "passive"))
      (node (ref "C236") (pin "1") (pinfunction "1_1") (pintype "passive"))
      (node (ref "C237") (pin "1") (pinfunction "1_1") (pintype "passive"))
      (node (ref "C238") (pin "2") (pinfunction "2_2") (pintype "passive"))
      (node (ref "C239") (pin "2") (pinfunction "2_2") (pintype "passive"))
      (node (ref "C245") (pin "1") (pinfunction "1_1") (pintype "passive"))
      (node (ref "C246") (pin "1") (pinfunction "1_1") (pintype "passive"))
      (node (ref "C247") (pin "1") (pinfunction "1_1") (pintype "passive"))
      (node (ref "C248") (pin "2") (pinfunction "2_2") (pintype "passive"))
      (node (ref "C249") (pin "2") (pinfunction "2_2") (pintype "passive"))
      (node (ref "C250") (pin "1") (pinfunction "1_1") (pintype "passive"))
      (node (ref "C251") (pin "1") (pinfunction "1_1") (pintype "passive"))
      (node (ref "C252") (pin "1") (pinfunction "1_1") (pintype "passive"))
      (node (ref "C254") (pin "2") (pinfunction "2_2") (pintype "passive"))
      (node (ref "C255") (pin "1") (pinfunction "1_1") (pintype "passive"))
      (node (ref "C256") (pin "2") (pinfunction "2_2") (pintype "passive"))
      (node (ref "C257") (pin "2") (pinfunction "2_2") (pintype "passive"))
      (node (ref "C258") (pin "2") (pinfunction "2_2") (pintype "passive"))
      (node (ref "C259") (pin "2") (pinfunction "2_2") (pintype "passive"))
      (node (ref "C260") (pin "2") (pinfunction "2_2") (pintype "passive"))
      (node (ref "C262") (pin "1") (pinfunction "1_1") (pintype "passive"))
      (node (ref "C263") (pin "1") (pinfunction "1_1") (pintype "passive"))
      (node (ref "C264") (pin "1") (pinfunction "1_1") (pintype "passive"))
      (node (ref "C265") (pin "1") (pinfunction "1_1") (pintype "passive"))
      (node (ref "C266") (pin "1") (pinfunction "1_1") (pintype "passive"))
      (node (ref "C267") (pin "1") (pinfunction "1_1") (pintype "passive"))
      (node (ref "C268") (pin "2") (pinfunction "2_2") (pintype "passive"))
      (node (ref "C269") (pin "1") (pinfunction "1_1") (pintype "passive"))
      (node (ref "C270") (pin "2") (pinfunction "2_2") (pintype "passive"))
      (node (ref "C271") (pin "2") (pinfunction "2_2") (pintype "passive"))
      (node (ref "C272") (pin "1") (pinfunction "1_1") (pintype "passive"))
      (node (ref "C273") (pin "2") (pinfunction "2_2") (pintype "passive"))
      (node (ref "C274") (pin "1") (pinfunction "1_1") (pintype "passive"))
      (node (ref "C275") (pin "2") (pinfunction "2_2") (pintype "passive"))
      (node (ref "C276") (pin "1") (pinfunction "1_1") (pintype "passive"))
      (node (ref "C277") (pin "2") (pinfunction "2_2") (pintype "passive"))
      (node (ref "C278") (pin "2") (pinfunction "2_2") (pintype "passive"))
      (node (ref "C279") (pin "2") (pinfunction "2_2") (pintype "passive"))
      (node (ref "C280") (pin "2") (pinfunction "2_2") (pintype "passive"))
      (node (ref "C281") (pin "1") (pinfunction "1_1") (pintype "passive"))
      (node (ref "C282") (pin "1") (pinfunction "1_1") (pintype "passive"))
      (node (ref "C283") (pin "1") (pinfunction "1_1") (pintype "passive"))
      (node (ref "C284") (pin "1") (pinfunction "1_1") (pintype "passive"))
      (node (ref "C285") (pin "1") (pinfunction "1_1") (pintype "passive"))
      (node (ref "C286") (pin "1") (pinfunction "1_1") (pintype "passive"))
      (node (ref "C287") (pin "1") (pinfunction "1_1") (pintype "passive"))
      (node (ref "C288") (pin "2") (pinfunction "2_2") (pintype "passive"))
      (node (ref "C289") (pin "2") (pinfunction "2_2") (pintype "passive"))
      (node (ref "C290") (pin "2") (pinfunction "2_2") (pintype "passive"))
      (node (ref "C291") (pin "2") (pinfunction "2_2") (pintype "passive"))
      (node (ref "C292") (pin "2") (pinfunction "2_2") (pintype "passive"))
      (node (ref "C294") (pin "2") (pinfunction "2_2") (pintype "passive"))
      (node (ref "C295") (pin "1") (pinfunction "1_1") (pintype "passive"))
      (node (ref "C296") (pin "2") (pinfunction "2_2") (pintype "passive"))
      (node (ref "C297") (pin "1") (pinfunction "1_1") (pintype "passive"))
      (node (ref "C298") (pin "1") (pinfunction "1_1") (pintype "passive"))
      (node (ref "C299") (pin "2") (pinfunction "2_2") (pintype "passive"))
      (node (ref "C300") (pin "2") (pinfunction "2_2") (pintype "passive"))
      (node (ref "C301") (pin "2") (pinfunction "2_2") (pintype "passive"))
      (node (ref "C302") (pin "2") (pinfunction "2_2") (pintype "passive"))
      (node (ref "C303") (pin "1") (pinfunction "1_1") (pintype "passive"))
      (node (ref "C304") (pin "2") (pinfunction "2_2") (pintype "passive"))
      (node (ref "C305") (pin "2") (pinfunction "2_2") (pintype "passive"))
      (node (ref "C306") (pin "2") (pinfunction "2_2") (pintype "passive"))
      (node (ref "C307") (pin "2") (pinfunction "2_2") (pintype "passive"))
      (node (ref "C310") (pin "1") (pinfunction "1_1") (pintype "passive"))
      (node (ref "C311") (pin "1") (pinfunction "1_1") (pintype "passive"))
      (node (ref "C312") (pin "1") (pinfunction "1_1") (pintype "passive"))
      (node (ref "C322") (pin "1") (pinfunction "1_1") (pintype "passive"))
      (node (ref "C323") (pin "2") (pinfunction "2_2") (pintype "passive"))
      (node (ref "C427") (pin "2") (pinfunction "2_2") (pintype "passive"))
      (node (ref "C428") (pin "2") (pinfunction "2_2") (pintype "passive"))
      (node (ref "C429") (pin "2") (pinfunction "2_2") (pintype "passive"))
      (node (ref "C430") (pin "1") (pinfunction "1_1") (pintype "passive"))
      (node (ref "C431") (pin "2") (pinfunction "2_2") (pintype "passive"))
      (node (ref "C432") (pin "2") (pinfunction "2_2") (pintype "passive"))
      (node (ref "IC32") (pin "5") (pinfunction "GND_5") (pintype "power_in"))
      (node (ref "IC34") (pin "5") (pinfunction "GND_5") (pintype "power_in"))
      (node (ref "IC35") (pin "5") (pinfunction "GND_5") (pintype "power_in"))
      (node (ref "IC37") (pin "5") (pinfunction "GND_5") (pintype "power_in"))
      (node (ref "IC38") (pin "2") (pinfunction "VSS_2") (pintype "power_in"))
      (node (ref "IC39") (pin "5") (pinfunction "GND_5") (pintype "power_in"))
      (node (ref "IC44") (pin "2") (pinfunction "VSS_2") (pintype "power_in"))
      (node (ref "IC46") (pin "12") (pinfunction "PGND2_12") (pintype "power_in"))
      (node (ref "IC46") (pin "19") (pinfunction "PGND1_19") (pintype "power_in"))
      (node (ref "IC46") (pin "25") (pinfunction "EP_25") (pintype "power_in"))
      (node (ref "IC46") (pin "3") (pinfunction "GND_3") (pintype "power_in"))
      (node (ref "IC46") (pin "4") (pinfunction "TEST1_4") (pintype "bidirectional"))
      (node (ref "IC47") (pin "12") (pinfunction "PGND2_12") (pintype "power_in"))
      (node (ref "IC47") (pin "19") (pinfunction "PGND1_19") (pintype "power_in"))
      (node (ref "IC47") (pin "25") (pinfunction "EP_25") (pintype "power_in"))
      (node (ref "IC47") (pin "3") (pinfunction "GND_3") (pintype "power_in"))
      (node (ref "IC47") (pin "4") (pinfunction "TEST1_4") (pintype "bidirectional"))
      (node (ref "IC48") (pin "5") (pinfunction "GND_5") (pintype "power_in"))
      (node (ref "R178") (pin "1") (pinfunction "1_1") (pintype "passive"))
      (node (ref "R185") (pin "1") (pinfunction "1_1") (pintype "passive"))
      (node (ref "R186") (pin "1") (pinfunction "1_1") (pintype "passive"))
      (node (ref "R196") (pin "1") (pinfunction "1_1") (pintype "passive"))
      (node (ref "R204") (pin "1") (pinfunction "1_1") (pintype "passive"))
      (node (ref "R209") (pin "2") (pinfunction "2_2") (pintype "passive"))
      (node (ref "R227") (pin "1") (pinfunction "1_1") (pintype "passive"))
      (node (ref "R229") (pin "2") (pinfunction "2_2") (pintype "passive"))
      (node (ref "R231") (pin "2") (pinfunction "2_2") (pintype "passive"))
      (node (ref "R232") (pin "2") (pinfunction "2_2") (pintype "passive"))
      (node (ref "R234") (pin "2") (pinfunction "2_2") (pintype "passive"))
      (node (ref "R235") (pin "1") (pinfunction "1_1") (pintype "passive"))
      (node (ref "R236") (pin "1") (pinfunction "1_1") (pintype "passive"))
      (node (ref "R238") (pin "2") (pinfunction "2_2") (pintype "passive"))
      (node (ref "R240") (pin "2") (pinfunction "2_2") (pintype "passive"))
      (node (ref "R242") (pin "2") (pinfunction "2_2") (pintype "passive"))
      (node (ref "T2") (pin "1") (pinfunction "S_1") (pintype "passive"))
      (node (ref "T3") (pin "1") (pinfunction "S_1") (pintype "passive"))
      (node (ref "T4") (pin "1") (pinfunction "S_1") (pintype "passive"))
      (node (ref "T5") (pin "1") (pinfunction "S_1") (pintype "passive"))
    )
    (net (code "24") (name "Net-(D3-A)") (class "Default")
      (node (ref "D3") (pin "1") (pinfunction "A_1") (pintype "passive"))
      (node (ref "IC47") (pin "7") (pinfunction "EN2_7") (pintype "input"))
      (node (ref "R243") (pin "1") (pinfunction "1_1") (pintype "passive"))
    )
    (net (code "25") (name "Net-(D3-K)") (class "Default")
      (node (ref "D3") (pin "2") (pinfunction "K_2") (pintype "passive"))
      (node (ref "D4") (pin "1") (pinfunction "A_1") (pintype "passive"))
    )
    (net (code "26") (name "Net-(IC32-FB)") (class "Default")
      (node (ref "IC32") (pin "7") (pinfunction "FB_7") (pintype "passive"))
      (node (ref "R178") (pin "2") (pinfunction "2_2") (pintype "passive"))
      (node (ref "R180") (pin "1") (pinfunction "1_1") (pintype "passive"))
    )
    (net (code "27") (name "Net-(IC32-SS)") (class "Default")
      (node (ref "C245") (pin "2") (pinfunction "2_2") (pintype "passive"))
      (node (ref "IC32") (pin "6") (pinfunction "SS_6") (pintype "passive"))
    )
    (net (code "28") (name "Net-(IC34-FB)") (class "Default")
      (node (ref "IC34") (pin "7") (pinfunction "FB_7") (pintype "passive"))
      (node (ref "R185") (pin "2") (pinfunction "2_2") (pintype "passive"))
      (node (ref "R188") (pin "2") (pinfunction "2_2") (pintype "passive"))
    )
    (net (code "29") (name "Net-(IC34-SS)") (class "Default")
      (node (ref "C262") (pin "2") (pinfunction "2_2") (pintype "passive"))
      (node (ref "IC34") (pin "6") (pinfunction "SS_6") (pintype "passive"))
    )
    (net (code "30") (name "Net-(IC35-FB)") (class "Default")
      (node (ref "IC35") (pin "7") (pinfunction "FB_7") (pintype "passive"))
      (node (ref "R186") (pin "2") (pinfunction "2_2") (pintype "passive"))
      (node (ref "R189") (pin "2") (pinfunction "2_2") (pintype "passive"))
    )
    (net (code "31") (name "Net-(IC35-SS)") (class "Default")
      (node (ref "C265") (pin "2") (pinfunction "2_2") (pintype "passive"))
      (node (ref "IC35") (pin "6") (pinfunction "SS_6") (pintype "passive"))
    )
    (net (code "32") (name "Net-(IC37-FB)") (class "Default")
      (node (ref "IC37") (pin "7") (pinfunction "FB_7") (pintype "passive"))
      (node (ref "R196") (pin "2") (pinfunction "2_2") (pintype "passive"))
      (node (ref "R198") (pin "1") (pinfunction "1_1") (pintype "passive"))
    )
    (net (code "33") (name "Net-(IC37-SS)") (class "Default")
      (node (ref "C284") (pin "2") (pinfunction "2_2") (pintype "passive"))
      (node (ref "IC37") (pin "6") (pinfunction "SS_6") (pintype "passive"))
    )
    (net (code "34") (name "Net-(IC39-FB)") (class "Default")
      (node (ref "IC39") (pin "7") (pinfunction "FB_7") (pintype "passive"))
      (node (ref "R204") (pin "2") (pinfunction "2_2") (pintype "passive"))
      (node (ref "R205") (pin "1") (pinfunction "1_1") (pintype "passive"))
    )
    (net (code "35") (name "Net-(IC39-SS)") (class "Default")
      (node (ref "C310") (pin "2") (pinfunction "2_2") (pintype "passive"))
      (node (ref "IC39") (pin "6") (pinfunction "SS_6") (pintype "passive"))
    )
    (net (code "36") (name "Net-(IC46-DRVH1)") (class "Default")
      (node (ref "IC46") (pin "22") (pinfunction "DRVH1_22") (pintype "output"))
      (node (ref "T3") (pin "4") (pinfunction "G_4") (pintype "passive"))
    )
    (net (code "37") (name "Net-(IC46-DRVH2)") (class "Default")
      (node (ref "IC46") (pin "9") (pinfunction "DRVH2_9") (pintype "output"))
      (node (ref "T2") (pin "4") (pinfunction "G_4") (pintype "passive"))
    )
    (net (code "38") (name "Net-(IC46-DRVL1)") (class "Default")
      (node (ref "IC46") (pin "20") (pinfunction "DRVL1_20") (pintype "output"))
      (node (ref "T3") (pin "2") (pinfunction "G_2") (pintype "passive"))
    )
    (net (code "39") (name "Net-(IC46-DRVL2)") (class "Default")
      (node (ref "IC46") (pin "11") (pinfunction "DRVL2_11") (pintype "output"))
      (node (ref "T2") (pin "2") (pinfunction "G_2") (pintype "passive"))
    )
    (net (code "40") (name "Net-(IC46-SW1)") (class "Default")
      (node (ref "C253") (pin "2") (pinfunction "2_2") (pintype "passive"))
      (node (ref "IC46") (pin "21") (pinfunction "SW1_21") (pintype "bidirectional"))
      (node (ref "L13") (pin "1") (pinfunction "1_1") (pintype "passive"))
      (node (ref "T3") (pin "3") (pinfunction "S_3") (pintype "passive"))
      (node (ref "T3") (pin "7") (pinfunction "D_7") (pintype "passive"))
      (node (ref "T3") (pin "8") (pinfunction "D_8") (pintype "passive"))
    )
    (net (code "41") (name "Net-(IC46-SW2)") (class "Default")
      (node (ref "C207") (pin "2") (pinfunction "2_2") (pintype "passive"))
      (node (ref "IC46") (pin "10") (pinfunction "SW2_10") (pintype "bidirectional"))
      (node (ref "L11") (pin "1") (pinfunction "1_1") (pintype "passive"))
      (node (ref "T2") (pin "3") (pinfunction "S_3") (pintype "passive"))
      (node (ref "T2") (pin "7") (pinfunction "D_7") (pintype "passive"))
      (node (ref "T2") (pin "8") (pinfunction "D_8") (pintype "passive"))
    )
    (net (code "42") (name "Net-(IC46-TEST2)") (class "Default")
      (node (ref "IC46") (pin "14") (pinfunction "TEST2_14") (pintype "input"))
      (node (ref "R210") (pin "2") (pinfunction "2_2") (pintype "passive"))
      (node (ref "R227") (pin "2") (pinfunction "2_2") (pintype "passive"))
    )
    (net (code "43") (name "Net-(IC46-TRIP1)") (class "Default")
      (node (ref "IC46") (pin "18") (pinfunction "TRIP1_18") (pintype "input"))
      (node (ref "R229") (pin "1") (pinfunction "1_1") (pintype "passive"))
    )
    (net (code "44") (name "Net-(IC46-TRIP2)") (class "Default")
      (node (ref "IC46") (pin "13") (pinfunction "TRIP2_13") (pintype "input"))
      (node (ref "R209") (pin "1") (pinfunction "1_1") (pintype "passive"))
    )
    (net (code "45") (name "Net-(IC46-V5FILT)") (class "Default")
      (node (ref "C237") (pin "2") (pinfunction "2_2") (pintype "passive"))
      (node (ref "IC46") (pin "15") (pinfunction "V5FILT_15") (pintype "input"))
      (node (ref "R210") (pin "1") (pinfunction "1_1") (pintype "passive"))
    )
    (net (code "46") (name "Net-(IC46-VBST1)") (class "Default")
      (node (ref "C253") (pin "1") (pinfunction "1_1") (pintype "passive"))
      (node (ref "IC46") (pin "23") (pinfunction "VBST1_23") (pintype "input"))
    )
    (net (code "47") (name "Net-(IC46-VBST2)") (class "Default")
      (node (ref "C207") (pin "1") (pinfunction "1_1") (pintype "passive"))
      (node (ref "IC46") (pin "8") (pinfunction "VBST2_8") (pintype "input"))
    )
    (net (code "48") (name "Net-(IC46-VFB1)") (class "Default")
      (node (ref "IC46") (pin "2") (pinfunction "VFB1_2") (pintype "input"))
      (node (ref "R230") (pin "1") (pinfunction "1_1") (pintype "passive"))
      (node (ref "R231") (pin "1") (pinfunction "1_1") (pintype "passive"))
    )
    (net (code "49") (name "Net-(IC46-VFB2)") (class "Default")
      (node (ref "IC46") (pin "5") (pinfunction "VFB2_5") (pintype "input"))
      (node (ref "R228") (pin "2") (pinfunction "2_2") (pintype "passive"))
      (node (ref "R238") (pin "1") (pinfunction "1_1") (pintype "passive"))
    )
    (net (code "50") (name "Net-(IC46-VREG5)") (class "Default")
      (node (ref "C238") (pin "1") (pinfunction "1_1") (pintype "passive"))
      (node (ref "IC46") (pin "16") (pinfunction "VREG5_16") (pintype "output"))
    )
    (net (code "51") (name "Net-(IC47-DRVH1)") (class "Default")
      (node (ref "IC47") (pin "22") (pinfunction "DRVH1_22") (pintype "output"))
      (node (ref "T5") (pin "4") (pinfunction "G_4") (pintype "passive"))
    )
    (net (code "52") (name "Net-(IC47-DRVH2)") (class "Default")
      (node (ref "IC47") (pin "9") (pinfunction "DRVH2_9") (pintype "output"))
      (node (ref "T4") (pin "4") (pinfunction "G_4") (pintype "passive"))
    )
    (net (code "53") (name "Net-(IC47-DRVL1)") (class "Default")
      (node (ref "IC47") (pin "20") (pinfunction "DRVL1_20") (pintype "output"))
      (node (ref "T5") (pin "2") (pinfunction "G_2") (pintype "passive"))
    )
    (net (code "54") (name "Net-(IC47-DRVL2)") (class "Default")
      (node (ref "IC47") (pin "11") (pinfunction "DRVL2_11") (pintype "output"))
      (node (ref "T4") (pin "2") (pinfunction "G_2") (pintype "passive"))
    )
    (net (code "55") (name "Net-(IC47-SW1)") (class "Default")
      (node (ref "C293") (pin "2") (pinfunction "2_2") (pintype "passive"))
      (node (ref "IC47") (pin "21") (pinfunction "SW1_21") (pintype "bidirectional"))
      (node (ref "L15") (pin "1") (pinfunction "1_1") (pintype "passive"))
      (node (ref "T5") (pin "3") (pinfunction "S_3") (pintype "passive"))
      (node (ref "T5") (pin "7") (pinfunction "D_7") (pintype "passive"))
      (node (ref "T5") (pin "8") (pinfunction "D_8") (pintype "passive"))
    )
    (net (code "56") (name "Net-(IC47-SW2)") (class "Default")
      (node (ref "C261") (pin "2") (pinfunction "2_2") (pintype "passive"))
      (node (ref "IC47") (pin "10") (pinfunction "SW2_10") (pintype "bidirectional"))
      (node (ref "L14") (pin "1") (pinfunction "1_1") (pintype "passive"))
      (node (ref "T4") (pin "3") (pinfunction "S_3") (pintype "passive"))
      (node (ref "T4") (pin "7") (pinfunction "D_7") (pintype "passive"))
      (node (ref "T4") (pin "8") (pinfunction "D_8") (pintype "passive"))
    )
    (net (code "57") (name "Net-(IC47-TEST2)") (class "Default")
      (node (ref "IC47") (pin "14") (pinfunction "TEST2_14") (pintype "input"))
      (node (ref "R233") (pin "2") (pinfunction "2_2") (pintype "passive"))
      (node (ref "R235") (pin "2") (pinfunction "2_2") (pintype "passive"))
    )
    (net (code "58") (name "Net-(IC47-TRIP1)") (class "Default")
      (node (ref "IC47") (pin "18") (pinfunction "TRIP1_18") (pintype "input"))
      (node (ref "R240") (pin "1") (pinfunction "1_1") (pintype "passive"))
    )
    (net (code "59") (name "Net-(IC47-TRIP2)") (class "Default")
      (node (ref "IC47") (pin "13") (pinfunction "TRIP2_13") (pintype "input"))
      (node (ref "R232") (pin "1") (pinfunction "1_1") (pintype "passive"))
    )
    (net (code "60") (name "Net-(IC47-V5FILT)") (class "Default")
      (node (ref "C272") (pin "2") (pinfunction "2_2") (pintype "passive"))
      (node (ref "IC47") (pin "15") (pinfunction "V5FILT_15") (pintype "input"))
      (node (ref "R233") (pin "1") (pinfunction "1_1") (pintype "passive"))
    )
    (net (code "61") (name "Net-(IC47-VBST1)") (class "Default")
      (node (ref "C293") (pin "1") (pinfunction "1_1") (pintype "passive"))
      (node (ref "IC47") (pin "23") (pinfunction "VBST1_23") (pintype "input"))
    )
    (net (code "62") (name "Net-(IC47-VBST2)") (class "Default")
      (node (ref "C261") (pin "1") (pinfunction "1_1") (pintype "passive"))
      (node (ref "IC47") (pin "8") (pinfunction "VBST2_8") (pintype "input"))
    )
    (net (code "63") (name "Net-(IC47-VFB1)") (class "Default")
      (node (ref "IC47") (pin "2") (pinfunction "VFB1_2") (pintype "input"))
      (node (ref "R241") (pin "1") (pinfunction "1_1") (pintype "passive"))
      (node (ref "R242") (pin "1") (pinfunction "1_1") (pintype "passive"))
    )
    (net (code "64") (name "Net-(IC47-VFB2)") (class "Default")
      (node (ref "IC47") (pin "5") (pinfunction "VFB2_5") (pintype "input"))
      (node (ref "R206") (pin "1") (pinfunction "1_1") (pintype "passive"))
      (node (ref "R234") (pin "1") (pinfunction "1_1") (pintype "passive"))
    )
    (net (code "65") (name "Net-(IC47-VREG5)") (class "Default")
      (node (ref "C273") (pin "1") (pinfunction "1_1") (pintype "passive"))
      (node (ref "IC47") (pin "16") (pinfunction "VREG5_16") (pintype "output"))
    )
    (net (code "66") (name "Net-(IC48-FB)") (class "Default")
      (node (ref "IC48") (pin "7") (pinfunction "FB_7") (pintype "passive"))
      (node (ref "R236") (pin "2") (pinfunction "2_2") (pintype "passive"))
      (node (ref "R237") (pin "1") (pinfunction "1_1") (pintype "passive"))
    )
    (net (code "67") (name "Net-(IC48-SS)") (class "Default")
      (node (ref "C282") (pin "2") (pinfunction "2_2") (pintype "passive"))
      (node (ref "IC48") (pin "6") (pinfunction "SS_6") (pintype "passive"))
    )
    (net (code "68") (name "unconnected-(IC38-NC-Pad4)") (class "Default")
      (node (ref "IC38") (pin "4") (pinfunction "NC_4") (pintype "passive+no_connect"))
    )
    (net (code "69") (name "unconnected-(IC44-NC-Pad4)") (class "Default")
      (node (ref "IC44") (pin "4") (pinfunction "NC_4") (pintype "passive+no_connect"))
    )
  )
)
